# RPi-Display_Bplus_v10.net
KiCad netlist of a schematic drawn in EAGLE
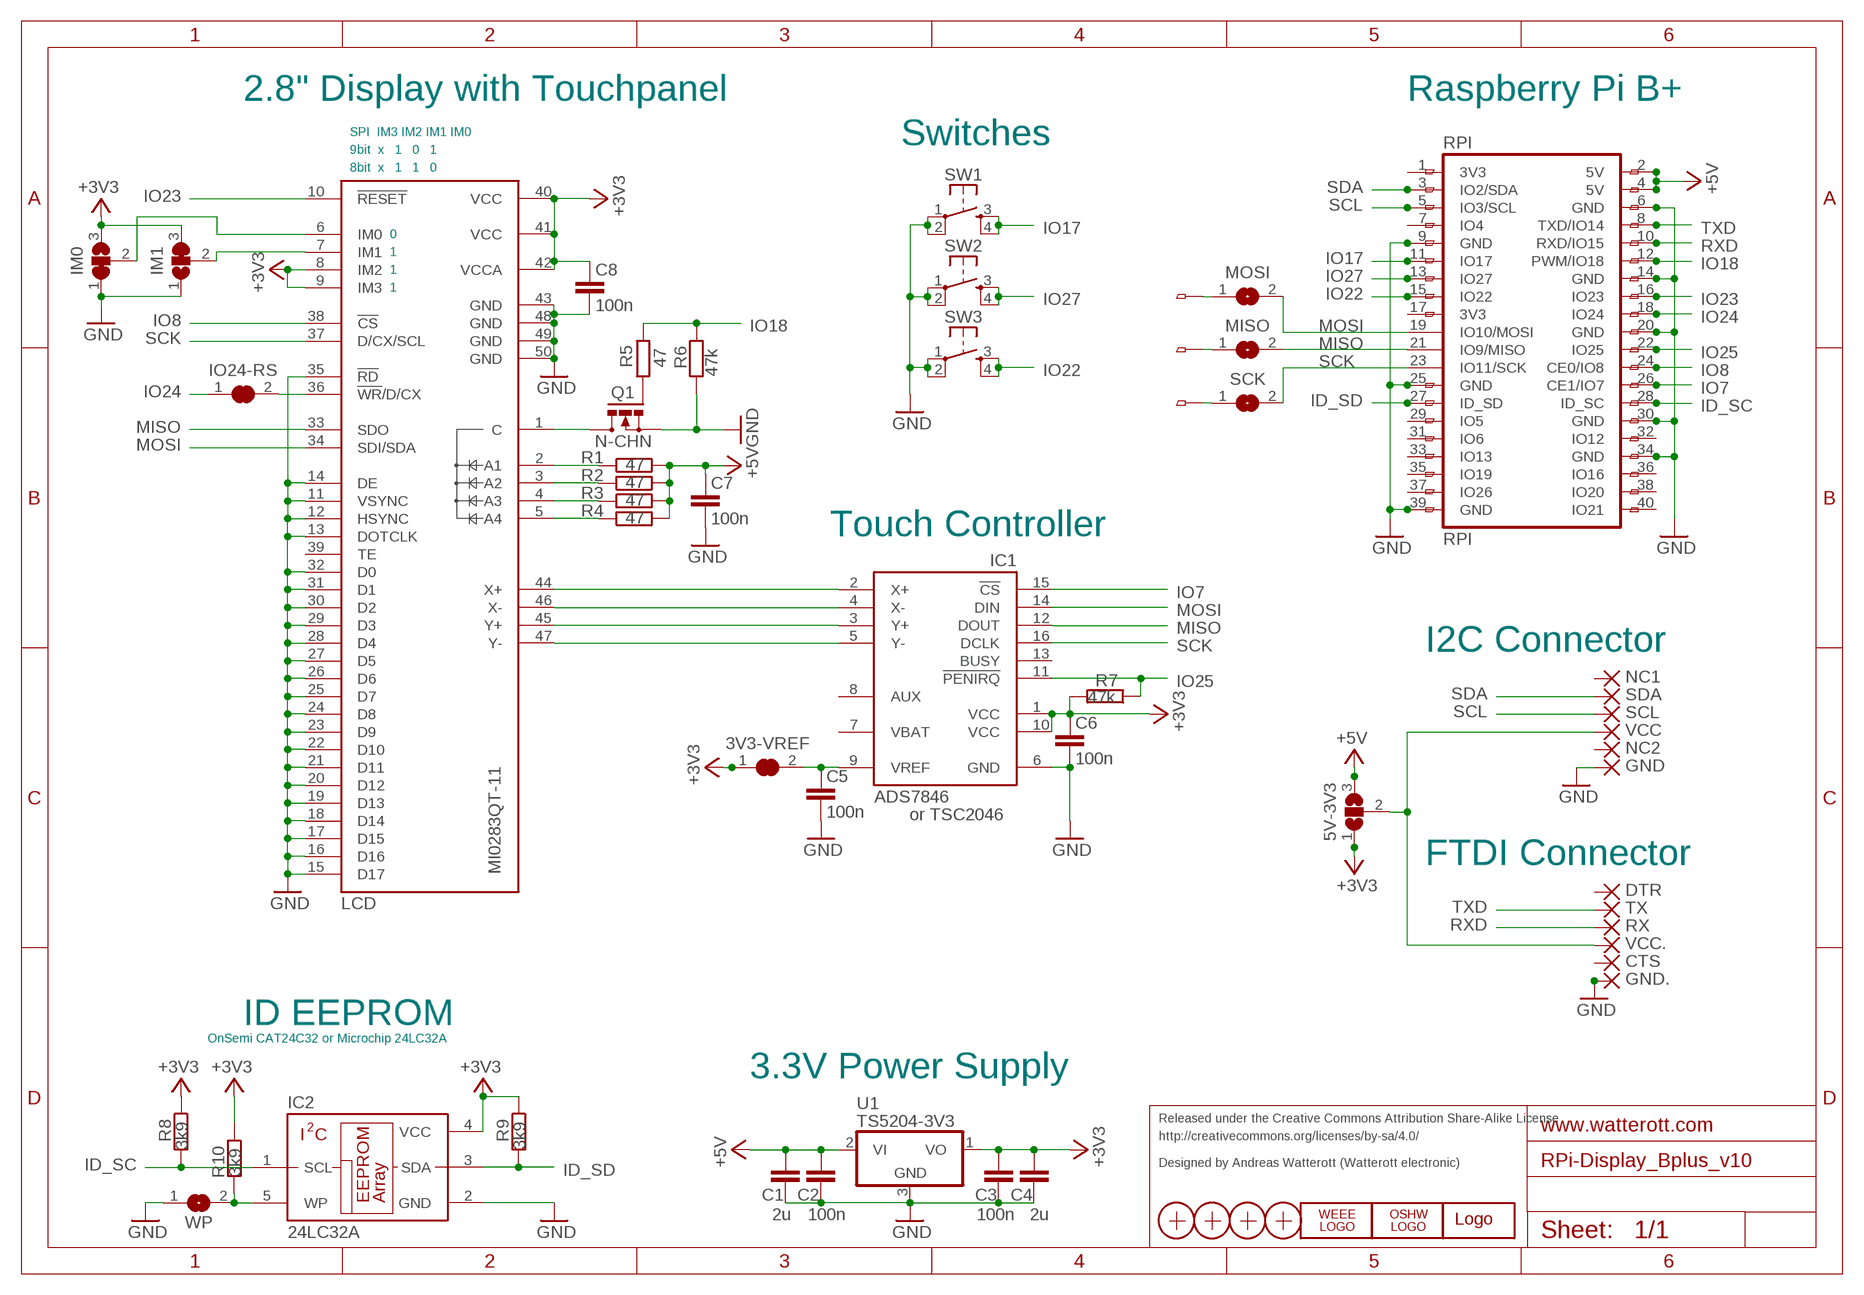
[diagram p0: schematic, sheet 1]

(export (version "E")
  (design (tool "Eeschema 10.0.6"))
  (components
    (comp (ref "3V3-VREF")
      (value "JUMPER2-NOCREAM")
      (footprint "eagle-import:JUMPER2_NC")
      (libsource (lib "eagle-import") (part "JUMPER2-NOCREAM"))
    )
    (comp (ref "5V-3V3")
      (value "JUMPER3-NOCREAM")
      (footprint "eagle-import:JUMPER3_NC")
      (libsource (lib "eagle-import") (part "JUMPER3-NOCREAM"))
    )
    (comp (ref "C1")
      (value "2u")
      (footprint "eagle-import:C0603")
      (libsource (lib "eagle-import") (part "C-EUC0603"))
    )
    (comp (ref "C2")
      (value "100n")
      (footprint "eagle-import:C0603")
      (libsource (lib "eagle-import") (part "C-EUC0603"))
    )
    (comp (ref "C3")
      (value "100n")
      (footprint "eagle-import:C0603")
      (libsource (lib "eagle-import") (part "C-EUC0603"))
    )
    (comp (ref "C4")
      (value "2u")
      (footprint "eagle-import:C0603")
      (libsource (lib "eagle-import") (part "C-EUC0603"))
    )
    (comp (ref "C5")
      (value "100n")
      (footprint "eagle-import:C0603")
      (libsource (lib "eagle-import") (part "C-EUC0603"))
    )
    (comp (ref "C6")
      (value "100n")
      (footprint "eagle-import:C0603")
      (libsource (lib "eagle-import") (part "C-EUC0603"))
    )
    (comp (ref "C7")
      (value "100n")
      (footprint "eagle-import:C0603")
      (libsource (lib "eagle-import") (part "C-EUC0603"))
    )
    (comp (ref "C8")
      (value "100n")
      (footprint "eagle-import:C0603")
      (libsource (lib "eagle-import") (part "C-EUC0603"))
    )
    (comp (ref "CTS")
      (value "PAD-1.27-NC")
      (footprint "eagle-import:PAD-1.27X2.54_NC")
      (libsource (lib "eagle-import") (part "PAD-1.27-NC"))
    )
    (comp (ref "DTR")
      (value "PAD-1.27-NC")
      (footprint "eagle-import:PAD-1.27X2.54_NC")
      (libsource (lib "eagle-import") (part "PAD-1.27-NC"))
    )
    (comp (ref "GND")
      (value "PAD-1.27-NC")
      (footprint "eagle-import:PAD-1.27X2.54_NC")
      (libsource (lib "eagle-import") (part "PAD-1.27-NC"))
    )
    (comp (ref "GND.")
      (value "PAD-1.27-NC")
      (footprint "eagle-import:PAD-1.27X2.54_NC")
      (libsource (lib "eagle-import") (part "PAD-1.27-NC"))
    )
    (comp (ref "GPIO")
      (value "FH12-40S-0.5SH")
      (footprint "eagle-import:FH12-40S-0.5SH")
      (fields (field (name "MPN") "FH12-40S-0.5SH(55)"))
      (libsource (lib "eagle-import") (part "FH12-40S-0.5SH"))
    )
    (comp (ref "IC1")
      (value "ADS7846")
      (footprint "eagle-import:SSOP16")
      (libsource (lib "eagle-import") (part "ADS7846"))
    )
    (comp (ref "IC2")
      (value "24LC32A")
      (footprint "eagle-import:SOT23-5")
      (libsource (lib "eagle-import") (part "I2C_EEPROM-CAT24AA0X"))
    )
    (comp (ref "IM0")
      (value "JUMPER3-NOCREAM")
      (footprint "eagle-import:JUMPER3_NC")
      (libsource (lib "eagle-import") (part "JUMPER3-NOCREAM"))
    )
    (comp (ref "IM1")
      (value "JUMPER3-NOCREAM")
      (footprint "eagle-import:JUMPER3_NC")
      (libsource (lib "eagle-import") (part "JUMPER3-NOCREAM"))
    )
    (comp (ref "IO24-RS")
      (value "JUMPER2-NOCREAM")
      (footprint "eagle-import:JUMPER2_NC")
      (libsource (lib "eagle-import") (part "JUMPER2-NOCREAM"))
    )
    (comp (ref "LCD")
      (value "MI0283QT-11")
      (footprint "eagle-import:MI0283QT11")
      (libsource (lib "eagle-import") (part "MI0283QT-11"))
    )
    (comp (ref "LOGO1")
      (value "OSHW_LOGO_6MILX0150-NT")
      (footprint "eagle-import:OSHW_6X150_NOTEXT")
      (libsource (lib "eagle-import") (part "OSHW_LOGO_6MILX0150-NT"))
    )
    (comp (ref "LOGO2")
      (value "WEEE_LOGO")
      (footprint "eagle-import:WEEE")
      (libsource (lib "eagle-import") (part "WEEE_LOGO"))
    )
    (comp (ref "MISO")
      (value "JUMPER2-NOCREAM")
      (footprint "eagle-import:JUMPER2_NC")
      (libsource (lib "eagle-import") (part "JUMPER2-NOCREAM"))
    )
    (comp (ref "MOSI")
      (value "JUMPER2-NOCREAM")
      (footprint "eagle-import:JUMPER2_NC")
      (libsource (lib "eagle-import") (part "JUMPER2-NOCREAM"))
    )
    (comp (ref "NC1")
      (value "PAD-1.27-NC")
      (footprint "eagle-import:PAD-1.27X2.54_NC")
      (libsource (lib "eagle-import") (part "PAD-1.27-NC"))
    )
    (comp (ref "NC2")
      (value "PAD-1.27-NC")
      (footprint "eagle-import:PAD-1.27X2.54_NC")
      (libsource (lib "eagle-import") (part "PAD-1.27-NC"))
    )
    (comp (ref "Q1")
      (value "N-CHN")
      (footprint "eagle-import:MICRO3")
      (libsource (lib "eagle-import") (part "IRLML2502"))
    )
    (comp (ref "R1")
      (value "47")
      (footprint "eagle-import:R0603")
      (libsource (lib "eagle-import") (part "R-EU_R0603"))
    )
    (comp (ref "R2")
      (value "47")
      (footprint "eagle-import:R0603")
      (libsource (lib "eagle-import") (part "R-EU_R0603"))
    )
    (comp (ref "R3")
      (value "47")
      (footprint "eagle-import:R0603")
      (libsource (lib "eagle-import") (part "R-EU_R0603"))
    )
    (comp (ref "R4")
      (value "47")
      (footprint "eagle-import:R0603")
      (libsource (lib "eagle-import") (part "R-EU_R0603"))
    )
    (comp (ref "R5")
      (value "47")
      (footprint "eagle-import:R0603")
      (libsource (lib "eagle-import") (part "R-EU_R0603"))
    )
    (comp (ref "R6")
      (value "47k")
      (footprint "eagle-import:R0603")
      (libsource (lib "eagle-import") (part "R-EU_R0603"))
    )
    (comp (ref "R7")
      (value "47k")
      (footprint "eagle-import:R0603")
      (libsource (lib "eagle-import") (part "R-EU_R0603"))
    )
    (comp (ref "R8")
      (value "3k9")
      (footprint "eagle-import:R0603")
      (libsource (lib "eagle-import") (part "R-EU_R0603"))
    )
    (comp (ref "R9")
      (value "3k9")
      (footprint "eagle-import:R0603")
      (libsource (lib "eagle-import") (part "R-EU_R0603"))
    )
    (comp (ref "R10")
      (value "3k9")
      (footprint "eagle-import:R0603")
      (libsource (lib "eagle-import") (part "R-EU_R0603"))
    )
    (comp (ref "RPI")
      (value "RPI")
      (footprint "eagle-import:RPI_B+")
      (libsource (lib "eagle-import") (part "RPI_B+"))
    )
    (comp (ref "RX")
      (value "PAD-1.27-NC")
      (footprint "eagle-import:PAD-1.27X2.54_NC")
      (libsource (lib "eagle-import") (part "PAD-1.27-NC"))
    )
    (comp (ref "SCK")
      (value "JUMPER2-NOCREAM")
      (footprint "eagle-import:JUMPER2_NC")
      (libsource (lib "eagle-import") (part "JUMPER2-NOCREAM"))
    )
    (comp (ref "SCL")
      (value "PAD-1.27-NC")
      (footprint "eagle-import:PAD-1.27X2.54_NC")
      (libsource (lib "eagle-import") (part "PAD-1.27-NC"))
    )
    (comp (ref "SDA")
      (value "PAD-1.27-NC")
      (footprint "eagle-import:PAD-1.27X2.54_NC")
      (libsource (lib "eagle-import") (part "PAD-1.27-NC"))
    )
    (comp (ref "SW1")
      (value "SWITCH-PTS840P")
      (footprint "eagle-import:SW_PTS840P")
      (libsource (lib "eagle-import") (part "SWITCH-PTS840P"))
    )
    (comp (ref "SW2")
      (value "SWITCH-PTS840P")
      (footprint "eagle-import:SW_PTS840P")
      (libsource (lib "eagle-import") (part "SWITCH-PTS840P"))
    )
    (comp (ref "SW3")
      (value "SWITCH-PTS840P")
      (footprint "eagle-import:SW_PTS840P")
      (libsource (lib "eagle-import") (part "SWITCH-PTS840P"))
    )
    (comp (ref "TX")
      (value "PAD-1.27-NC")
      (footprint "eagle-import:PAD-1.27X2.54_NC")
      (libsource (lib "eagle-import") (part "PAD-1.27-NC"))
    )
    (comp (ref "U$1")
      (value "WE-LOGO")
      (footprint "eagle-import:WE-LOGO")
      (libsource (lib "eagle-import") (part "WE-LOGOPLACE"))
    )
    (comp (ref "U1")
      (value "TS5204-3V3")
      (footprint "eagle-import:SOT23")
      (libsource (lib "eagle-import") (part "TS5204"))
    )
    (comp (ref "VCC")
      (value "PAD-1.27-NC")
      (footprint "eagle-import:PAD-1.27X2.54_NC")
      (libsource (lib "eagle-import") (part "PAD-1.27-NC"))
    )
    (comp (ref "VCC.")
      (value "PAD-1.27-NC")
      (footprint "eagle-import:PAD-1.27X2.54_NC")
      (libsource (lib "eagle-import") (part "PAD-1.27-NC"))
    )
    (comp (ref "WP")
      (value "JUMPER2-NOCREAM")
      (footprint "eagle-import:JUMPER2_NC")
      (libsource (lib "eagle-import") (part "JUMPER2-NOCREAM"))
    )
    (comp (ref "X1")
      (value "PASSER")
      (footprint "eagle-import:PASSER")
      (libsource (lib "eagle-import") (part "PASSER"))
    )
    (comp (ref "X2")
      (value "PASSER")
      (footprint "eagle-import:PASSER")
      (libsource (lib "eagle-import") (part "PASSER"))
    )
    (comp (ref "X3")
      (value "PASSER")
      (footprint "eagle-import:PASSER")
      (libsource (lib "eagle-import") (part "PASSER"))
    )
    (comp (ref "X4")
      (value "PASSER")
      (footprint "eagle-import:PASSER")
      (libsource (lib "eagle-import") (part "PASSER"))
    )
  )
  (nets
    (net (code "1") (name "+3V3") (class "Default")
      (node (ref "3V3-VREF") (pin "1") (pinfunction "1_1") (pintype "passive"))
      (node (ref "5V-3V3") (pin "1") (pinfunction "1_1") (pintype "passive"))
      (node (ref "C3") (pin "1") (pinfunction "1_1") (pintype "passive"))
      (node (ref "C4") (pin "1") (pinfunction "1_1") (pintype "passive"))
      (node (ref "C6") (pin "1") (pinfunction "1_1") (pintype "passive"))
      (node (ref "C8") (pin "1") (pinfunction "1_1") (pintype "passive"))
      (node (ref "IC1") (pin "1") (pinfunction "VCC_1") (pintype "power_in"))
      (node (ref "IC1") (pin "10") (pinfunction "VCC_10") (pintype "power_in"))
      (node (ref "IC2") (pin "4") (pinfunction "VCC_4") (pintype "power_in"))
      (node (ref "IM0") (pin "3") (pinfunction "3_3") (pintype "passive"))
      (node (ref "IM1") (pin "3") (pinfunction "3_3") (pintype "passive"))
      (node (ref "LCD") (pin "40") (pinfunction "VCC_40") (pintype "power_in"))
      (node (ref "LCD") (pin "41") (pinfunction "VCC_41") (pintype "power_in"))
      (node (ref "LCD") (pin "42") (pinfunction "VCCA_42") (pintype "power_in"))
      (node (ref "LCD") (pin "8") (pinfunction "IM2_8") (pintype "input"))
      (node (ref "LCD") (pin "9") (pinfunction "IM3_9") (pintype "input"))
      (node (ref "R10") (pin "1") (pinfunction "1_1") (pintype "passive"))
      (node (ref "R7") (pin "2") (pinfunction "2_2") (pintype "passive"))
      (node (ref "R8") (pin "1") (pinfunction "1_1") (pintype "passive"))
      (node (ref "R9") (pin "1") (pinfunction "1_1") (pintype "passive"))
      (node (ref "U1") (pin "1") (pinfunction "VO_1") (pintype "passive"))
    )
    (net (code "2") (name "+5V") (class "Default")
      (node (ref "5V-3V3") (pin "3") (pinfunction "3_3") (pintype "passive"))
      (node (ref "C1") (pin "1") (pinfunction "1_1") (pintype "passive"))
      (node (ref "C2") (pin "1") (pinfunction "1_1") (pintype "passive"))
      (node (ref "C7") (pin "1") (pinfunction "1_1") (pintype "passive"))
      (node (ref "GPIO") (pin "37") (pinfunction "1_37") (pintype "passive"))
      (node (ref "GPIO") (pin "39") (pinfunction "1_39") (pintype "passive"))
      (node (ref "R1") (pin "2") (pinfunction "2_2") (pintype "passive"))
      (node (ref "R2") (pin "2") (pinfunction "2_2") (pintype "passive"))
      (node (ref "R3") (pin "2") (pinfunction "2_2") (pintype "passive"))
      (node (ref "R4") (pin "2") (pinfunction "2_2") (pintype "passive"))
      (node (ref "RPI") (pin "2") (pinfunction "5V_2") (pintype "passive"))
      (node (ref "RPI") (pin "4") (pinfunction "5V_4") (pintype "passive"))
      (node (ref "U1") (pin "2") (pinfunction "VI_2") (pintype "input"))
    )
    (net (code "3") (name "/ID_SC") (class "Default")
      (node (ref "GPIO") (pin "13") (pinfunction "1_13") (pintype "passive"))
      (node (ref "IC2") (pin "1") (pinfunction "SCL_1") (pintype "bidirectional"))
      (node (ref "R8") (pin "2") (pinfunction "2_2") (pintype "passive"))
      (node (ref "RPI") (pin "28") (pinfunction "ID_SC_28") (pintype "bidirectional"))
    )
    (net (code "4") (name "/ID_SD") (class "Default")
      (node (ref "GPIO") (pin "14") (pinfunction "1_14") (pintype "passive"))
      (node (ref "IC2") (pin "3") (pinfunction "SDA_3") (pintype "bidirectional"))
      (node (ref "R9") (pin "2") (pinfunction "2_2") (pintype "passive"))
      (node (ref "RPI") (pin "27") (pinfunction "ID_SD_27") (pintype "bidirectional"))
    )
    (net (code "5") (name "/IO7") (class "Default")
      (node (ref "GPIO") (pin "15") (pinfunction "1_15") (pintype "passive"))
      (node (ref "IC1") (pin "15") (pinfunction "~{CS}_15") (pintype "input"))
      (node (ref "RPI") (pin "26") (pinfunction "CE1/IO7_26") (pintype "passive"))
    )
    (net (code "6") (name "/IO8") (class "Default")
      (node (ref "GPIO") (pin "17") (pinfunction "1_17") (pintype "passive"))
      (node (ref "LCD") (pin "38") (pinfunction "~{CS}_38") (pintype "input"))
      (node (ref "RPI") (pin "24") (pinfunction "CE0/IO8_24") (pintype "passive"))
    )
    (net (code "7") (name "/IO17") (class "Default")
      (node (ref "GPIO") (pin "30") (pinfunction "1_30") (pintype "passive"))
      (node (ref "RPI") (pin "11") (pinfunction "IO17_11") (pintype "passive"))
      (node (ref "SW1") (pin "3") (pinfunction "S_3") (pintype "passive"))
      (node (ref "SW1") (pin "4") (pinfunction "S1_4") (pintype "passive"))
    )
    (net (code "8") (name "/IO18") (class "Default")
      (node (ref "GPIO") (pin "29") (pinfunction "1_29") (pintype "passive"))
      (node (ref "R5") (pin "2") (pinfunction "2_2") (pintype "passive"))
      (node (ref "R6") (pin "1") (pinfunction "1_1") (pintype "passive"))
      (node (ref "RPI") (pin "12") (pinfunction "PWM/IO18_12") (pintype "passive"))
    )
    (net (code "9") (name "/IO22") (class "Default")
      (node (ref "GPIO") (pin "26") (pinfunction "1_26") (pintype "passive"))
      (node (ref "RPI") (pin "15") (pinfunction "IO22_15") (pintype "passive"))
      (node (ref "SW3") (pin "3") (pinfunction "S_3") (pintype "passive"))
      (node (ref "SW3") (pin "4") (pinfunction "S1_4") (pintype "passive"))
    )
    (net (code "10") (name "/IO23") (class "Default")
      (node (ref "GPIO") (pin "25") (pinfunction "1_25") (pintype "passive"))
      (node (ref "LCD") (pin "10") (pinfunction "~{RESET}_10") (pintype "input"))
      (node (ref "RPI") (pin "16") (pinfunction "IO23_16") (pintype "passive"))
    )
    (net (code "11") (name "/IO24") (class "Default")
      (node (ref "GPIO") (pin "23") (pinfunction "1_23") (pintype "passive"))
      (node (ref "IO24-RS") (pin "1") (pinfunction "1_1") (pintype "passive"))
      (node (ref "RPI") (pin "18") (pinfunction "IO24_18") (pintype "passive"))
    )
    (net (code "12") (name "/IO25") (class "Default")
      (node (ref "GPIO") (pin "19") (pinfunction "1_19") (pintype "passive"))
      (node (ref "IC1") (pin "11") (pinfunction "~{PENIRQ}_11") (pintype "output"))
      (node (ref "R7") (pin "1") (pinfunction "1_1") (pintype "passive"))
      (node (ref "RPI") (pin "22") (pinfunction "IO25_22") (pintype "passive"))
    )
    (net (code "13") (name "/IO27") (class "Default")
      (node (ref "GPIO") (pin "28") (pinfunction "1_28") (pintype "passive"))
      (node (ref "RPI") (pin "13") (pinfunction "IO27_13") (pintype "passive"))
      (node (ref "SW2") (pin "3") (pinfunction "S_3") (pintype "passive"))
      (node (ref "SW2") (pin "4") (pinfunction "S1_4") (pintype "passive"))
    )
    (net (code "14") (name "/MISO") (class "Default")
      (node (ref "IC1") (pin "12") (pinfunction "DOUT_12") (pintype "input"))
      (node (ref "LCD") (pin "33") (pinfunction "SDO_33") (pintype "output"))
      (node (ref "MISO") (pin "2") (pinfunction "2_2") (pintype "passive"))
      (node (ref "RPI") (pin "21") (pinfunction "IO9/MISO_21") (pintype "passive"))
    )
    (net (code "15") (name "/MOSI") (class "Default")
      (node (ref "IC1") (pin "14") (pinfunction "DIN_14") (pintype "input"))
      (node (ref "LCD") (pin "34") (pinfunction "SDI/SDA_34") (pintype "input"))
      (node (ref "MOSI") (pin "2") (pinfunction "2_2") (pintype "passive"))
      (node (ref "RPI") (pin "19") (pinfunction "IO10/MOSI_19") (pintype "passive"))
    )
    (net (code "16") (name "/RXD") (class "Default")
      (node (ref "GPIO") (pin "31") (pinfunction "1_31") (pintype "passive"))
      (node (ref "RPI") (pin "10") (pinfunction "RXD/IO15_10") (pintype "passive"))
      (node (ref "RX") (pin "1") (pinfunction "P_1") (pintype "passive"))
    )
    (net (code "17") (name "/SCK") (class "Default")
      (node (ref "IC1") (pin "16") (pinfunction "DCLK_16") (pintype "output"))
      (node (ref "LCD") (pin "37") (pinfunction "D/CX/SCL_37") (pintype "input"))
      (node (ref "RPI") (pin "23") (pinfunction "IO11/SCK_23") (pintype "passive"))
      (node (ref "SCK") (pin "2") (pinfunction "2_2") (pintype "passive"))
    )
    (net (code "18") (name "/SCL") (class "Default")
      (node (ref "GPIO") (pin "36") (pinfunction "1_36") (pintype "passive"))
      (node (ref "RPI") (pin "5") (pinfunction "IO3/SCL_5") (pintype "passive"))
      (node (ref "SCL") (pin "1") (pinfunction "P_1") (pintype "passive"))
    )
    (net (code "19") (name "/SDA") (class "Default")
      (node (ref "GPIO") (pin "38") (pinfunction "1_38") (pintype "passive"))
      (node (ref "RPI") (pin "3") (pinfunction "IO2/SDA_3") (pintype "passive"))
      (node (ref "SDA") (pin "1") (pinfunction "P_1") (pintype "passive"))
    )
    (net (code "20") (name "/TXD") (class "Default")
      (node (ref "GPIO") (pin "33") (pinfunction "1_33") (pintype "passive"))
      (node (ref "RPI") (pin "8") (pinfunction "TXD/IO14_8") (pintype "passive"))
      (node (ref "TX") (pin "1") (pinfunction "P_1") (pintype "passive"))
    )
    (net (code "21") (name "GND") (class "Default")
      (node (ref "C1") (pin "2") (pinfunction "2_2") (pintype "passive"))
      (node (ref "C2") (pin "2") (pinfunction "2_2") (pintype "passive"))
      (node (ref "C3") (pin "2") (pinfunction "2_2") (pintype "passive"))
      (node (ref "C4") (pin "2") (pinfunction "2_2") (pintype "passive"))
      (node (ref "C5") (pin "2") (pinfunction "2_2") (pintype "passive"))
      (node (ref "C6") (pin "2") (pinfunction "2_2") (pintype "passive"))
      (node (ref "C7") (pin "2") (pinfunction "2_2") (pintype "passive"))
      (node (ref "C8") (pin "2") (pinfunction "2_2") (pintype "passive"))
      (node (ref "GND") (pin "1") (pinfunction "P_1") (pintype "passive"))
      (node (ref "GND.") (pin "1") (pinfunction "P_1") (pintype "passive"))
      (node (ref "GPIO") (pin "11") (pinfunction "1_11") (pintype "passive"))
      (node (ref "GPIO") (pin "16") (pinfunction "1_16") (pintype "passive"))
      (node (ref "GPIO") (pin "2") (pinfunction "1_2") (pintype "passive"))
      (node (ref "GPIO") (pin "21") (pinfunction "1_21") (pintype "passive"))
      (node (ref "GPIO") (pin "27") (pinfunction "1_27") (pintype "passive"))
      (node (ref "GPIO") (pin "32") (pinfunction "1_32") (pintype "passive"))
      (node (ref "GPIO") (pin "35") (pinfunction "1_35") (pintype "passive"))
      (node (ref "GPIO") (pin "7") (pinfunction "1_7") (pintype "passive"))
      (node (ref "IC1") (pin "6") (pinfunction "GND_6") (pintype "power_in"))
      (node (ref "IC2") (pin "2") (pinfunction "GND_2") (pintype "power_in"))
      (node (ref "IM0") (pin "1") (pinfunction "1_1") (pintype "passive"))
      (node (ref "IM1") (pin "1") (pinfunction "1_1") (pintype "passive"))
      (node (ref "LCD") (pin "11") (pinfunction "VSYNC_11") (pintype "input"))
      (node (ref "LCD") (pin "12") (pinfunction "HSYNC_12") (pintype "input"))
      (node (ref "LCD") (pin "13") (pinfunction "DOTCLK_13") (pintype "input"))
      (node (ref "LCD") (pin "14") (pinfunction "DE_14") (pintype "input"))
      (node (ref "LCD") (pin "15") (pinfunction "D17_15") (pintype "input"))
      (node (ref "LCD") (pin "16") (pinfunction "D16_16") (pintype "input"))
      (node (ref "LCD") (pin "17") (pinfunction "D15_17") (pintype "input"))
      (node (ref "LCD") (pin "18") (pinfunction "D14_18") (pintype "input"))
      (node (ref "LCD") (pin "19") (pinfunction "D13_19") (pintype "input"))
      (node (ref "LCD") (pin "20") (pinfunction "D12_20") (pintype "input"))
      (node (ref "LCD") (pin "21") (pinfunction "D11_21") (pintype "input"))
      (node (ref "LCD") (pin "22") (pinfunction "D10_22") (pintype "input"))
      (node (ref "LCD") (pin "23") (pinfunction "D9_23") (pintype "input"))
      (node (ref "LCD") (pin "24") (pinfunction "D8_24") (pintype "input"))
      (node (ref "LCD") (pin "25") (pinfunction "D7_25") (pintype "input"))
      (node (ref "LCD") (pin "26") (pinfunction "D6_26") (pintype "input"))
      (node (ref "LCD") (pin "27") (pinfunction "D5_27") (pintype "input"))
      (node (ref "LCD") (pin "28") (pinfunction "D4_28") (pintype "input"))
      (node (ref "LCD") (pin "29") (pinfunction "D3_29") (pintype "input"))
      (node (ref "LCD") (pin "30") (pinfunction "D2_30") (pintype "input"))
      (node (ref "LCD") (pin "31") (pinfunction "D1_31") (pintype "input"))
      (node (ref "LCD") (pin "32") (pinfunction "D0_32") (pintype "input"))
      (node (ref "LCD") (pin "35") (pinfunction "~{RD}_35") (pintype "input"))
      (node (ref "LCD") (pin "43") (pinfunction "GND_43") (pintype "power_in"))
      (node (ref "LCD") (pin "48") (pinfunction "GND_48") (pintype "power_in"))
      (node (ref "LCD") (pin "49") (pinfunction "GND_49") (pintype "power_in"))
      (node (ref "LCD") (pin "50") (pinfunction "GND_50") (pintype "power_in"))
      (node (ref "Q1") (pin "2") (pinfunction "S_2") (pintype "passive"))
      (node (ref "R6") (pin "2") (pinfunction "2_2") (pintype "passive"))
      (node (ref "RPI") (pin "14") (pinfunction "GND_14") (pintype "passive"))
      (node (ref "RPI") (pin "20") (pinfunction "GND_20") (pintype "passive"))
      (node (ref "RPI") (pin "25") (pinfunction "GND_25") (pintype "passive"))
      (node (ref "RPI") (pin "30") (pinfunction "GND_30") (pintype "bidirectional"))
      (node (ref "RPI") (pin "34") (pinfunction "GND_34") (pintype "bidirectional"))
      (node (ref "RPI") (pin "39") (pinfunction "GND_39") (pintype "bidirectional"))
      (node (ref "RPI") (pin "6") (pinfunction "GND_6") (pintype "passive"))
      (node (ref "RPI") (pin "9") (pinfunction "GND_9") (pintype "passive"))
      (node (ref "SW1") (pin "1") (pinfunction "P_1") (pintype "passive"))
      (node (ref "SW1") (pin "2") (pinfunction "P1_2") (pintype "passive"))
      (node (ref "SW2") (pin "1") (pinfunction "P_1") (pintype "passive"))
      (node (ref "SW2") (pin "2") (pinfunction "P1_2") (pintype "passive"))
      (node (ref "SW3") (pin "1") (pinfunction "P_1") (pintype "passive"))
      (node (ref "SW3") (pin "2") (pinfunction "P1_2") (pintype "passive"))
      (node (ref "U1") (pin "3") (pinfunction "GND_3") (pintype "passive"))
      (node (ref "WP") (pin "1") (pinfunction "1_1") (pintype "passive"))
    )
    (net (code "22") (name "Net-(GPIOAB-1)") (class "Default")
      (node (ref "GPIO") (pin "34") (pinfunction "1_34") (pintype "passive"))
      (node (ref "RPI") (pin "7") (pinfunction "IO4_7") (pintype "passive"))
    )
    (net (code "23") (name "Net-(GPIOAH-1)") (class "Default")
      (node (ref "GPIO") (pin "4") (pinfunction "1_4") (pintype "passive"))
      (node (ref "RPI") (pin "37") (pinfunction "IO26_37") (pintype "bidirectional"))
    )
    (net (code "24") (name "Net-(GPIOAI-1)") (class "Default")
      (node (ref "GPIO") (pin "40") (pinfunction "1_40") (pintype "passive"))
      (node (ref "RPI") (pin "1") (pinfunction "3V3_1") (pintype "passive"))
    )
    (net (code "25") (name "Net-(GPIOAJ-1)") (class "Default")
      (node (ref "GPIO") (pin "5") (pinfunction "1_5") (pintype "passive"))
      (node (ref "RPI") (pin "36") (pinfunction "IO16_36") (pintype "bidirectional"))
    )
    (net (code "26") (name "Net-(GPIOAK-1)") (class "Default")
      (node (ref "GPIO") (pin "6") (pinfunction "1_6") (pintype "passive"))
      (node (ref "RPI") (pin "35") (pinfunction "IO19_35") (pintype "bidirectional"))
    )
    (net (code "27") (name "Net-(GPIOAM-1)") (class "Default")
      (node (ref "GPIO") (pin "8") (pinfunction "1_8") (pintype "passive"))
      (node (ref "RPI") (pin "33") (pinfunction "IO13_33") (pintype "bidirectional"))
    )
    (net (code "28") (name "Net-(GPIOAN-1)") (class "Default")
      (node (ref "GPIO") (pin "9") (pinfunction "1_9") (pintype "passive"))
      (node (ref "RPI") (pin "32") (pinfunction "IO12_32") (pintype "bidirectional"))
    )
    (net (code "29") (name "Net-(GPIOB-1)") (class "Default")
      (node (ref "GPIO") (pin "10") (pinfunction "1_10") (pintype "passive"))
      (node (ref "RPI") (pin "31") (pinfunction "IO6_31") (pintype "bidirectional"))
    )
    (net (code "30") (name "Net-(GPIOD-1)") (class "Default")
      (node (ref "GPIO") (pin "12") (pinfunction "1_12") (pintype "passive"))
      (node (ref "RPI") (pin "29") (pinfunction "IO5_29") (pintype "bidirectional"))
    )
    (net (code "31") (name "Net-(GPIOJ-1)") (class "Default")
      (node (ref "GPIO") (pin "18") (pinfunction "1_18") (pintype "passive"))
      (node (ref "SCK") (pin "1") (pinfunction "1_1") (pintype "passive"))
    )
    (net (code "32") (name "Net-(GPIOM-1)") (class "Default")
      (node (ref "GPIO") (pin "20") (pinfunction "1_20") (pintype "passive"))
      (node (ref "MISO") (pin "1") (pinfunction "1_1") (pintype "passive"))
    )
    (net (code "33") (name "Net-(GPIOO-1)") (class "Default")
      (node (ref "GPIO") (pin "22") (pinfunction "1_22") (pintype "passive"))
      (node (ref "MOSI") (pin "1") (pinfunction "1_1") (pintype "passive"))
    )
    (net (code "34") (name "Net-(GPIOQ-1)") (class "Default")
      (node (ref "GPIO") (pin "24") (pinfunction "1_24") (pintype "passive"))
      (node (ref "RPI") (pin "17") (pinfunction "3V3_17") (pintype "passive"))
    )
    (net (code "35") (name "Net-(GPIOW-1)") (class "Default")
      (node (ref "GPIO") (pin "3") (pinfunction "1_3") (pintype "passive"))
      (node (ref "RPI") (pin "38") (pinfunction "IO20_38") (pintype "bidirectional"))
    )
    (net (code "36") (name "Net-(IC1-VREF)") (class "Default")
      (node (ref "3V3-VREF") (pin "2") (pinfunction "2_2") (pintype "passive"))
      (node (ref "C5") (pin "1") (pinfunction "1_1") (pintype "passive"))
      (node (ref "IC1") (pin "9") (pinfunction "VREF_9") (pintype "bidirectional"))
    )
    (net (code "37") (name "Net-(IC1-X+)") (class "Default")
      (node (ref "IC1") (pin "2") (pinfunction "X+_2") (pintype "input"))
      (node (ref "LCD") (pin "44") (pinfunction "X+_44") (pintype "passive"))
    )
    (net (code "38") (name "Net-(IC1-X-)") (class "Default")
      (node (ref "IC1") (pin "4") (pinfunction "X-_4") (pintype "input"))
      (node (ref "LCD") (pin "46") (pinfunction "X-_46") (pintype "passive"))
    )
    (net (code "39") (name "Net-(IC1-Y+)") (class "Default")
      (node (ref "IC1") (pin "3") (pinfunction "Y+_3") (pintype "input"))
      (node (ref "LCD") (pin "45") (pinfunction "Y+_45") (pintype "passive"))
    )
    (net (code "40") (name "Net-(IC1-Y-)") (class "Default")
      (node (ref "IC1") (pin "5") (pinfunction "Y-_5") (pintype "input"))
      (node (ref "LCD") (pin "47") (pinfunction "Y-_47") (pintype "passive"))
    )
    (net (code "41") (name "Net-(IC2-WP)") (class "Default")
      (node (ref "IC2") (pin "5") (pinfunction "WP_5") (pintype "bidirectional"))
      (node (ref "R10") (pin "2") (pinfunction "2_2") (pintype "passive"))
      (node (ref "WP") (pin "2") (pinfunction "2_2") (pintype "passive"))
    )
    (net (code "42") (name "Net-(LCD-A1)") (class "Default")
      (node (ref "LCD") (pin "2") (pinfunction "A1_2") (pintype "power_in"))
      (node (ref "R1") (pin "1") (pinfunction "1_1") (pintype "passive"))
    )
    (net (code "43") (name "Net-(LCD-A2)") (class "Default")
      (node (ref "LCD") (pin "3") (pinfunction "A2_3") (pintype "power_in"))
      (node (ref "R2") (pin "1") (pinfunction "1_1") (pintype "passive"))
    )
    (net (code "44") (name "Net-(LCD-A3)") (class "Default")
      (node (ref "LCD") (pin "4") (pinfunction "A3_4") (pintype "power_in"))
      (node (ref "R3") (pin "1") (pinfunction "1_1") (pintype "passive"))
    )
    (net (code "45") (name "Net-(LCD-A4)") (class "Default")
      (node (ref "LCD") (pin "5") (pinfunction "A4_5") (pintype "power_in"))
      (node (ref "R4") (pin "1") (pinfunction "1_1") (pintype "passive"))
    )
    (net (code "46") (name "Net-(LCD-C)") (class "Default")
      (node (ref "LCD") (pin "1") (pinfunction "C_1") (pintype "power_in"))
      (node (ref "Q1") (pin "3") (pinfunction "D_3") (pintype "passive"))
    )
    (net (code "47") (name "Net-(LCD-IM0)") (class "Default")
      (node (ref "IM0") (pin "2") (pinfunction "2_2") (pintype "passive"))
      (node (ref "LCD") (pin "6") (pinfunction "IM0_6") (pintype "input"))
    )
    (net (code "48") (name "Net-(LCD-IM1)") (class "Default")
      (node (ref "IM1") (pin "2") (pinfunction "2_2") (pintype "passive"))
      (node (ref "LCD") (pin "7") (pinfunction "IM1_7") (pintype "input"))
    )
    (net (code "49") (name "Net-(LCD-~{WR}{slash}D{slash}CX)") (class "Default")
      (node (ref "IO24-RS") (pin "2") (pinfunction "2_2") (pintype "passive"))
      (node (ref "LCD") (pin "36") (pinfunction "~{WR}/D/CX_36") (pintype "input"))
    )
    (net (code "50") (name "Net-(Q1-G)") (class "Default")
      (node (ref "Q1") (pin "1") (pinfunction "G_1") (pintype "passive"))
      (node (ref "R5") (pin "1") (pinfunction "1_1") (pintype "passive"))
    )
    (net (code "51") (name "Net-(RPI-IO21)") (class "Default")
      (node (ref "GPIO") (pin "1") (pinfunction "1_1") (pintype "passive"))
      (node (ref "RPI") (pin "40") (pinfunction "IO21_40") (pintype "bidirectional"))
    )
    (net (code "52") (name "Net-(VCC-P)") (class "Default")
      (node (ref "5V-3V3") (pin "2") (pinfunction "2_2") (pintype "passive"))
      (node (ref "VCC") (pin "1") (pinfunction "P_1") (pintype "passive"))
      (node (ref "VCC.") (pin "1") (pinfunction "P_1") (pintype "passive"))
    )
    (net (code "53") (name "unconnected-(CTS-P-Pad1)") (class "Default")
      (node (ref "CTS") (pin "1") (pinfunction "P_1") (pintype "passive"))
    )
    (net (code "54") (name "unconnected-(DTR-P-Pad1)") (class "Default")
      (node (ref "DTR") (pin "1") (pinfunction "P_1") (pintype "passive"))
    )
    (net (code "55") (name "unconnected-(IC1-AUX-Pad8)") (class "Default")
      (node (ref "IC1") (pin "8") (pinfunction "AUX_8") (pintype "input"))
    )
    (net (code "56") (name "unconnected-(IC1-BUSY-Pad13)") (class "Default")
      (node (ref "IC1") (pin "13") (pinfunction "BUSY_13") (pintype "output"))
    )
    (net (code "57") (name "unconnected-(IC1-VBAT-Pad7)") (class "Default")
      (node (ref "IC1") (pin "7") (pinfunction "VBAT_7") (pintype "input"))
    )
    (net (code "58") (name "unconnected-(LCD-TE-Pad39)") (class "Default")
      (node (ref "LCD") (pin "39") (pinfunction "TE_39") (pintype "output"))
    )
    (net (code "59") (name "unconnected-(NC1-P-Pad1)") (class "Default")
      (node (ref "NC1") (pin "1") (pinfunction "P_1") (pintype "passive"))
    )
    (net (code "60") (name "unconnected-(NC2-P-Pad1)") (class "Default")
      (node (ref "NC2") (pin "1") (pinfunction "P_1") (pintype "passive"))
    )
  )
)
